# lpc11c14.net
KiCad netlist of a schematic drawn in Altium Designer
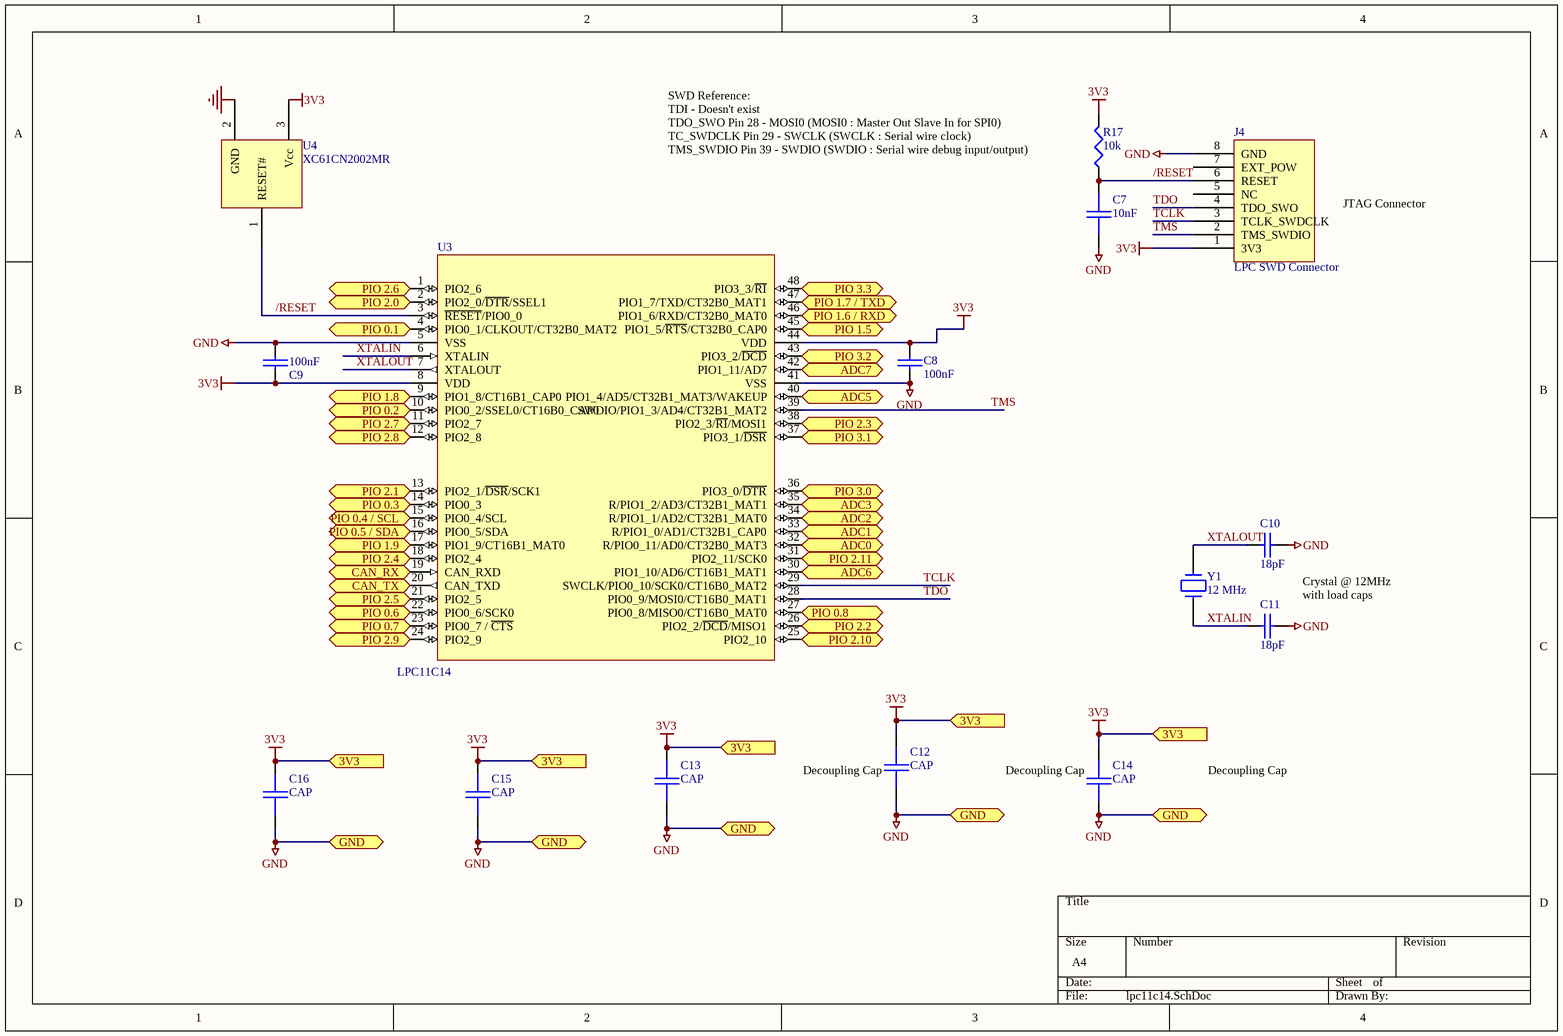
[diagram p0: lpc11c14.SchDoc]

(export (version "E")
  (design (tool "Eeschema 10.0.6"))
  (components
    (comp (ref "C7")
      (value "10nF")
      (footprint "0603")
      (description "Capacitor")
      (libsource (lib "SunswiftLib20030312RR") (part "CAP"))
    )
    (comp (ref "C8")
      (value "100nF")
      (footprint "0603")
      (description "Capacitor")
      (libsource (lib "*") (part "CAP"))
    )
    (comp (ref "C9")
      (value "100nF")
      (footprint "0603")
      (description "Capacitor")
      (libsource (lib "*") (part "CAP"))
    )
    (comp (ref "C10")
      (value "18pF")
      (footprint "0603")
      (description "Capacitor")
      (libsource (lib "*") (part "CAP"))
    )
    (comp (ref "C11")
      (value "18pF")
      (footprint "0603")
      (description "Capacitor")
      (libsource (lib "*") (part "CAP"))
    )
    (comp (ref "C12")
      (value "CAP")
      (footprint "0603")
      (description "Capacitor")
      (libsource (lib "RCLDQ") (part "CAP"))
    )
    (comp (ref "C13")
      (value "CAP")
      (footprint "0603")
      (description "Capacitor")
      (libsource (lib "RCLDQ") (part "CAP"))
    )
    (comp (ref "C14")
      (value "CAP")
      (footprint "0603")
      (description "Capacitor")
      (libsource (lib "RCLDQ") (part "CAP"))
    )
    (comp (ref "C15")
      (value "CAP")
      (footprint "0603")
      (description "Capacitor")
      (libsource (lib "RCLDQ") (part "CAP"))
    )
    (comp (ref "C16")
      (value "CAP")
      (footprint "0603")
      (description "Capacitor")
      (libsource (lib "RCLDQ") (part "CAP"))
    )
    (comp (ref "J4")
      (value "LPC SWD Connector")
      (footprint "HDR1X8")
      (libsource (lib "2009_BatteryMaster") (part "LPCLink_Connector"))
    )
    (comp (ref "R17")
      (value "10k")
      (footprint "0603")
      (description "Resistor")
      (libsource (lib "SunswiftLib20030312RR") (part "RES1"))
    )
    (comp (ref "U3")
      (value "LPC11C14")
      (footprint "QFP48-long")
      (libsource (lib "LPC") (part "LPC11C14_Full"))
    )
    (comp (ref "U4")
      (value "XC61CN2002MR")
      (footprint "SOT23-3")
      (description "SOT23 reset generator")
      (libsource (lib "*") (part "XC61F"))
    )
    (comp (ref "Y1")
      (value "12 MHz")
      (footprint "HC49/4H")
      (description "Crystal")
      (libsource (lib "*") (part "CRYSTAL"))
    )
  )
  (nets
    (net (code "1") (name "/ADC0") (class "Default")
      (node (ref "U3") (pin "32") (pinfunction "R/PIO0_11/AD0/CT32B0_MAT3_32") (pintype "bidirectional"))
    )
    (net (code "2") (name "/ADC1") (class "Default")
      (node (ref "U3") (pin "33") (pinfunction "R/PIO1_0/AD1/CT32B1_CAP0_33") (pintype "bidirectional"))
    )
    (net (code "3") (name "/ADC2") (class "Default")
      (node (ref "U3") (pin "34") (pinfunction "R/PIO1_1/AD2/CT32B1_MAT0_34") (pintype "bidirectional"))
    )
    (net (code "4") (name "/ADC3") (class "Default")
      (node (ref "U3") (pin "35") (pinfunction "R/PIO1_2/AD3/CT32B1_MAT1_35") (pintype "bidirectional"))
    )
    (net (code "5") (name "/ADC5") (class "Default")
      (node (ref "U3") (pin "40") (pinfunction "PIO1_4/AD5/CT32B1_MAT3/WAKEUP_40") (pintype "bidirectional"))
    )
    (net (code "6") (name "/ADC6") (class "Default")
      (node (ref "U3") (pin "30") (pinfunction "PIO1_10/AD6/CT16B1_MAT1_30") (pintype "bidirectional"))
    )
    (net (code "7") (name "/ADC7") (class "Default")
      (node (ref "U3") (pin "42") (pinfunction "PIO1_11/AD7_42") (pintype "bidirectional"))
    )
    (net (code "8") (name "/CAN_RX") (class "Default")
      (node (ref "U3") (pin "19") (pinfunction "CAN_RXD_19") (pintype "input"))
    )
    (net (code "9") (name "/CAN_TX") (class "Default")
      (node (ref "U3") (pin "20") (pinfunction "CAN_TXD_20") (pintype "output"))
    )
    (net (code "10") (name "/PIO 0.1") (class "Default")
      (node (ref "U3") (pin "4") (pinfunction "PIO0_1/CLKOUT/CT32B0_MAT2_4") (pintype "bidirectional"))
    )
    (net (code "11") (name "/PIO 0.2") (class "Default")
      (node (ref "U3") (pin "10") (pinfunction "PIO0_2/SSEL0/CT16B0_CAP0_10") (pintype "bidirectional"))
    )
    (net (code "12") (name "/PIO 0.3") (class "Default")
      (node (ref "U3") (pin "14") (pinfunction "PIO0_3_14") (pintype "bidirectional"))
    )
    (net (code "13") (name "/PIO 0.4 {slash} SCL") (class "Default")
      (node (ref "U3") (pin "15") (pinfunction "PIO0_4/SCL_15") (pintype "bidirectional"))
    )
    (net (code "14") (name "/PIO 0.5 {slash} SDA") (class "Default")
      (node (ref "U3") (pin "16") (pinfunction "PIO0_5/SDA_16") (pintype "bidirectional"))
    )
    (net (code "15") (name "/PIO 0.6") (class "Default")
      (node (ref "U3") (pin "22") (pinfunction "PIO0_6/SCK0_22") (pintype "bidirectional"))
    )
    (net (code "16") (name "/PIO 0.7") (class "Default")
      (node (ref "U3") (pin "23") (pinfunction "PIO0_7_/_~{CTS}_23") (pintype "bidirectional"))
    )
    (net (code "17") (name "/PIO 0.8") (class "Default")
      (node (ref "U3") (pin "27") (pinfunction "PIO0_8/MISO0/CT16B0_MAT0_27") (pintype "bidirectional"))
    )
    (net (code "18") (name "/PIO 1.5") (class "Default")
      (node (ref "U3") (pin "45") (pinfunction "PIO1_5/~{RTS}/CT32B0_CAP0_45") (pintype "bidirectional"))
    )
    (net (code "19") (name "/PIO 1.6 {slash} RXD") (class "Default")
      (node (ref "U3") (pin "46") (pinfunction "PIO1_6/RXD/CT32B0_MAT0_46") (pintype "bidirectional"))
    )
    (net (code "20") (name "/PIO 1.7 {slash} TXD") (class "Default")
      (node (ref "U3") (pin "47") (pinfunction "PIO1_7/TXD/CT32B0_MAT1_47") (pintype "bidirectional"))
    )
    (net (code "21") (name "/PIO 1.8") (class "Default")
      (node (ref "U3") (pin "9") (pinfunction "PIO1_8/CT16B1_CAP0_9") (pintype "bidirectional"))
    )
    (net (code "22") (name "/PIO 1.9") (class "Default")
      (node (ref "U3") (pin "17") (pinfunction "PIO1_9/CT16B1_MAT0_17") (pintype "bidirectional"))
    )
    (net (code "23") (name "/PIO 2.0") (class "Default")
      (node (ref "U3") (pin "2") (pinfunction "PIO2_0/~{DTR}/SSEL1_2") (pintype "bidirectional"))
    )
    (net (code "24") (name "/PIO 2.1") (class "Default")
      (node (ref "U3") (pin "13") (pinfunction "PIO2_1/~{DSR}/SCK1_13") (pintype "bidirectional"))
    )
    (net (code "25") (name "/PIO 2.2") (class "Default")
      (node (ref "U3") (pin "26") (pinfunction "PIO2_2/~{DCD}/MISO1_26") (pintype "bidirectional"))
    )
    (net (code "26") (name "/PIO 2.3") (class "Default")
      (node (ref "U3") (pin "38") (pinfunction "PIO2_3/~{RI}/MOSI1_38") (pintype "bidirectional"))
    )
    (net (code "27") (name "/PIO 2.4") (class "Default")
      (node (ref "U3") (pin "18") (pinfunction "PIO2_4_18") (pintype "bidirectional"))
    )
    (net (code "28") (name "/PIO 2.5") (class "Default")
      (node (ref "U3") (pin "21") (pinfunction "PIO2_5_21") (pintype "bidirectional"))
    )
    (net (code "29") (name "/PIO 2.6") (class "Default")
      (node (ref "U3") (pin "1") (pinfunction "PIO2_6_1") (pintype "bidirectional"))
    )
    (net (code "30") (name "/PIO 2.7") (class "Default")
      (node (ref "U3") (pin "11") (pinfunction "PIO2_7_11") (pintype "bidirectional"))
    )
    (net (code "31") (name "/PIO 2.8") (class "Default")
      (node (ref "U3") (pin "12") (pinfunction "PIO2_8_12") (pintype "bidirectional"))
    )
    (net (code "32") (name "/PIO 2.9") (class "Default")
      (node (ref "U3") (pin "24") (pinfunction "PIO2_9_24") (pintype "bidirectional"))
    )
    (net (code "33") (name "/PIO 2.10") (class "Default")
      (node (ref "U3") (pin "25") (pinfunction "PIO2_10_25") (pintype "bidirectional"))
    )
    (net (code "34") (name "/PIO 2.11") (class "Default")
      (node (ref "U3") (pin "31") (pinfunction "PIO2_11/SCK0_31") (pintype "bidirectional"))
    )
    (net (code "35") (name "/PIO 3.0") (class "Default")
      (node (ref "U3") (pin "36") (pinfunction "PIO3_0/~{DTR}_36") (pintype "bidirectional"))
    )
    (net (code "36") (name "/PIO 3.1") (class "Default")
      (node (ref "U3") (pin "37") (pinfunction "PIO3_1/~{DSR}_37") (pintype "bidirectional"))
    )
    (net (code "37") (name "/PIO 3.2") (class "Default")
      (node (ref "U3") (pin "43") (pinfunction "PIO3_2/~{DCD}_43") (pintype "bidirectional"))
    )
    (net (code "38") (name "/PIO 3.3") (class "Default")
      (node (ref "U3") (pin "48") (pinfunction "PIO3_3/~{RI}_48") (pintype "bidirectional"))
    )
    (net (code "39") (name "/TCLK") (class "Default")
      (node (ref "J4") (pin "3") (pinfunction "TCLK_SWDCLK_3") (pintype "passive"))
      (node (ref "U3") (pin "29") (pinfunction "SWCLK/PIO0_10/SCK0/CT16B0_MAT2_29") (pintype "bidirectional"))
    )
    (net (code "40") (name "/TDO") (class "Default")
      (node (ref "J4") (pin "4") (pinfunction "TDO_SWO_4") (pintype "passive"))
      (node (ref "U3") (pin "28") (pinfunction "PIO0_9/MOSI0/CT16B0_MAT1_28") (pintype "bidirectional"))
    )
    (net (code "41") (name "/TMS") (class "Default")
      (node (ref "J4") (pin "2") (pinfunction "TMS_SWDIO_2") (pintype "passive"))
      (node (ref "U3") (pin "39") (pinfunction "SWDIO/PIO1_3/AD4/CT32B1_MAT2_39") (pintype "bidirectional"))
    )
    (net (code "42") (name "/XTALIN") (class "Default")
      (node (ref "C11") (pin "1") (pinfunction "1_1") (pintype "passive"))
      (node (ref "U3") (pin "6") (pinfunction "XTALIN_6") (pintype "input"))
      (node (ref "Y1") (pin "1") (pinfunction "1_1") (pintype "passive"))
    )
    (net (code "43") (name "/XTALOUT") (class "Default")
      (node (ref "C10") (pin "1") (pinfunction "1_1") (pintype "passive"))
      (node (ref "U3") (pin "7") (pinfunction "XTALOUT_7") (pintype "output"))
      (node (ref "Y1") (pin "2") (pinfunction "2_2") (pintype "passive"))
    )
    (net (code "44") (name "/{slash}RESET") (class "Default")
      (node (ref "C7") (pin "1") (pinfunction "1_1") (pintype "passive"))
      (node (ref "J4") (pin "6") (pinfunction "RESET_6") (pintype "passive"))
      (node (ref "R17") (pin "1") (pinfunction "1_1") (pintype "passive"))
      (node (ref "U3") (pin "3") (pinfunction "~{RESET}/PIO0_0_3") (pintype "bidirectional"))
      (node (ref "U4") (pin "1") (pinfunction "RESET#_1") (pintype "passive"))
    )
    (net (code "45") (name "3V3") (class "Default")
      (node (ref "C12") (pin "1") (pinfunction "1_1") (pintype "passive"))
      (node (ref "C13") (pin "1") (pinfunction "1_1") (pintype "passive"))
      (node (ref "C14") (pin "1") (pinfunction "1_1") (pintype "passive"))
      (node (ref "C15") (pin "1") (pinfunction "1_1") (pintype "passive"))
      (node (ref "C16") (pin "1") (pinfunction "1_1") (pintype "passive"))
      (node (ref "C8") (pin "1") (pinfunction "1_1") (pintype "passive"))
      (node (ref "C9") (pin "2") (pinfunction "2_2") (pintype "passive"))
      (node (ref "J4") (pin "1") (pinfunction "3V3_1") (pintype "passive"))
      (node (ref "R17") (pin "2") (pinfunction "2_2") (pintype "passive"))
      (node (ref "U3") (pin "44") (pinfunction "VDD_44") (pintype "power_in"))
      (node (ref "U3") (pin "8") (pinfunction "VDD_8") (pintype "power_in"))
      (node (ref "U4") (pin "3") (pinfunction "Vcc_3") (pintype "passive"))
    )
    (net (code "46") (name "GND") (class "Default")
      (node (ref "C10") (pin "2") (pinfunction "2_2") (pintype "passive"))
      (node (ref "C11") (pin "2") (pinfunction "2_2") (pintype "passive"))
      (node (ref "C12") (pin "2") (pinfunction "2_2") (pintype "passive"))
      (node (ref "C13") (pin "2") (pinfunction "2_2") (pintype "passive"))
      (node (ref "C14") (pin "2") (pinfunction "2_2") (pintype "passive"))
      (node (ref "C15") (pin "2") (pinfunction "2_2") (pintype "passive"))
      (node (ref "C16") (pin "2") (pinfunction "2_2") (pintype "passive"))
      (node (ref "C7") (pin "2") (pinfunction "2_2") (pintype "passive"))
      (node (ref "C8") (pin "2") (pinfunction "2_2") (pintype "passive"))
      (node (ref "C9") (pin "1") (pinfunction "1_1") (pintype "passive"))
      (node (ref "J4") (pin "8") (pinfunction "GND_8") (pintype "passive"))
      (node (ref "U3") (pin "41") (pinfunction "VSS_41") (pintype "power_in"))
      (node (ref "U3") (pin "5") (pinfunction "VSS_5") (pintype "power_in"))
      (node (ref "U4") (pin "2") (pinfunction "GND_2") (pintype "passive"))
    )
    (net (code "47") (name "unconnected-(J4-EXT_POW-Pad7)") (class "Default")
      (node (ref "J4") (pin "7") (pinfunction "EXT_POW_7") (pintype "passive"))
    )
    (net (code "48") (name "unconnected-(J4-NC-Pad5)") (class "Default")
      (node (ref "J4") (pin "5") (pinfunction "NC_5") (pintype "passive"))
    )
  )
)
